# BaiDoXe_CamBien.net
KiCad netlist of a schematic drawn in Altium Designer
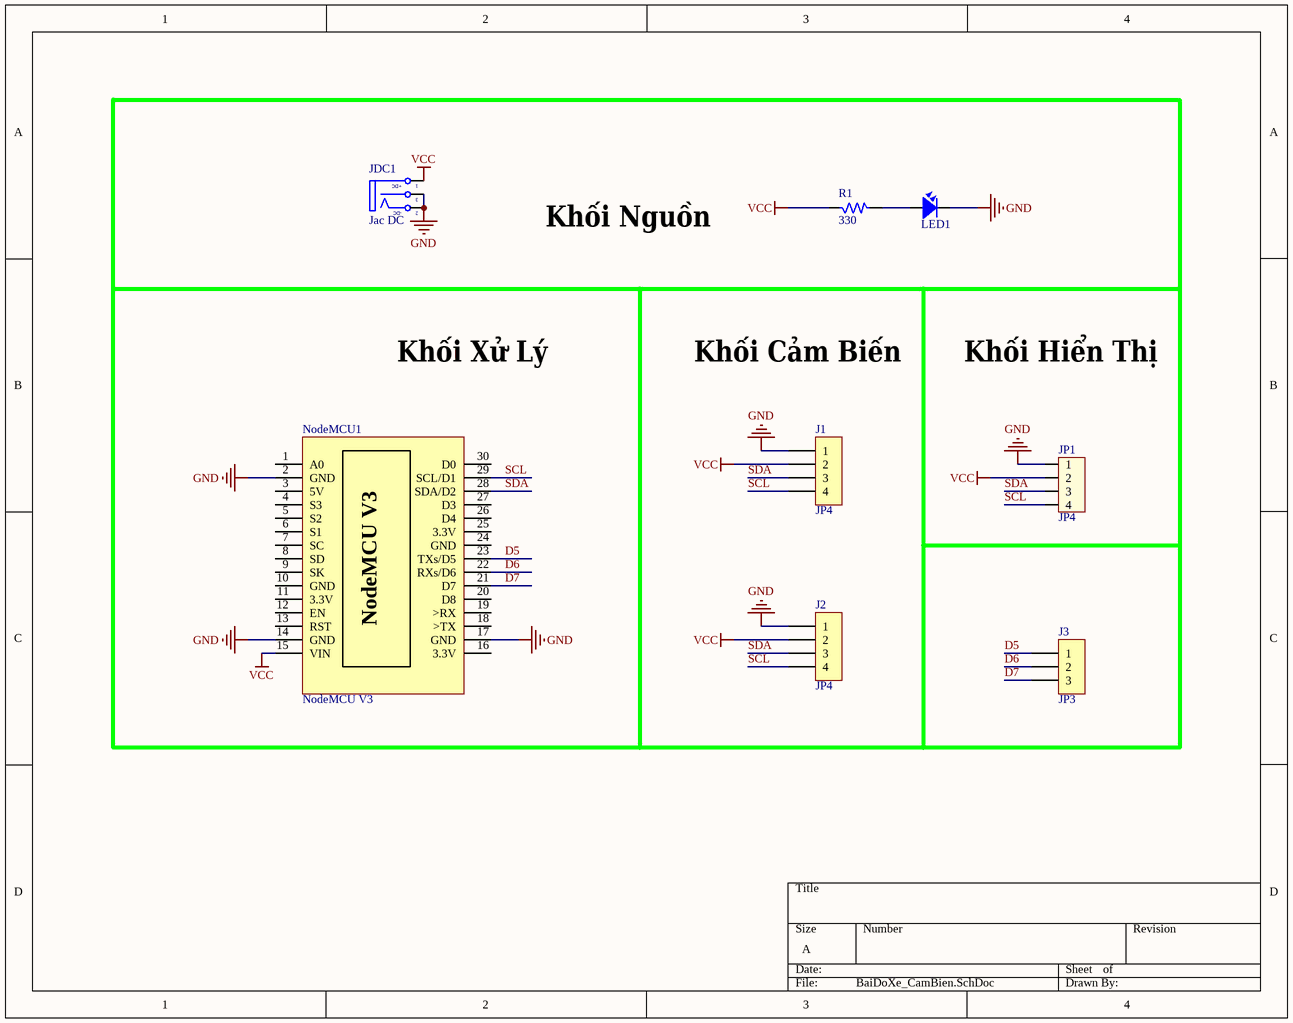
[diagram p0: BaiDoXe_CamBien.SchDoc]

(export (version "E")
  (design (tool "Eeschema 10.0.6"))
  (components
    (comp (ref "J1")
      (value "JP4")
      (footprint "JUMP DON 4")
      (description "JUMP DON DUC 2.54")
      (libsource (lib "LinhKienMCU.com") (part "JUMP 4"))
    )
    (comp (ref "J2")
      (value "JP4")
      (footprint "JUMP DON 4")
      (description "JUMP DON DUC 2.54")
      (libsource (lib "LinhKienMCU.com") (part "JUMP 4"))
    )
    (comp (ref "J3")
      (value "JP3")
      (footprint "JUMP DON 3")
      (description "JUMP DON DUC 2.54")
      (libsource (lib "LinhKienMCU.com") (part "JUMP 3"))
    )
    (comp (ref "JDC1")
      (value "Jac DC")
      (footprint "DC-IN")
      (description "Jac DC input")
      (libsource (lib "syhaunguyen") (part "DCIN"))
    )
    (comp (ref "JP1")
      (value "JP4")
      (footprint "CON4")
      (description "Connector 4")
      (libsource (lib "syhaunguyen") (part "Con4"))
    )
    (comp (ref "LED1")
      (value "LED")
      (footprint "LED-5-BLUE")
      (description "LED Single colour Green and Red")
      (libsource (lib "syhaunguyen") (part "LED"))
    )
    (comp (ref "NodeMCU1")
      (value "NodeMCU V3")
      (footprint "NodeMCU-V3")
      (libsource (lib "TDX_Local_LIbrary") (part "NodeMCU-V3"))
    )
    (comp (ref "R1")
      (value "330")
      (footprint "res_0805")
      (description "TRO DAN 0805")
      (libsource (lib "LinhKienMCU.com") (part "RES 0805"))
    )
  )
  (nets
    (net (code "1") (name "/D5") (class "Default")
      (node (ref "J3") (pin "1") (pinfunction "1_1") (pintype "passive"))
      (node (ref "NodeMCU1") (pin "23") (pinfunction "TXs/D5_23") (pintype "passive"))
    )
    (net (code "2") (name "/D6") (class "Default")
      (node (ref "J3") (pin "2") (pinfunction "2_2") (pintype "passive"))
      (node (ref "NodeMCU1") (pin "22") (pinfunction "RXs/D6_22") (pintype "passive"))
    )
    (net (code "3") (name "/D7") (class "Default")
      (node (ref "J3") (pin "3") (pinfunction "3_3") (pintype "passive"))
      (node (ref "NodeMCU1") (pin "21") (pinfunction "D7_21") (pintype "passive"))
    )
    (net (code "4") (name "/SCL") (class "Default")
      (node (ref "J1") (pin "4") (pinfunction "4_4") (pintype "passive"))
      (node (ref "J2") (pin "4") (pinfunction "4_4") (pintype "passive"))
      (node (ref "JP1") (pin "4") (pinfunction "4_4") (pintype "passive"))
      (node (ref "NodeMCU1") (pin "29") (pinfunction "SCL/D1_29") (pintype "passive"))
    )
    (net (code "5") (name "/SDA") (class "Default")
      (node (ref "J1") (pin "3") (pinfunction "3_3") (pintype "passive"))
      (node (ref "J2") (pin "3") (pinfunction "3_3") (pintype "passive"))
      (node (ref "JP1") (pin "3") (pinfunction "3_3") (pintype "passive"))
      (node (ref "NodeMCU1") (pin "28") (pinfunction "SDA/D2_28") (pintype "passive"))
    )
    (net (code "6") (name "GND") (class "Default")
      (node (ref "J1") (pin "1") (pinfunction "1_1") (pintype "passive"))
      (node (ref "J2") (pin "1") (pinfunction "1_1") (pintype "passive"))
      (node (ref "JDC1") (pin "2") (pinfunction "TN_2") (pintype "passive"))
      (node (ref "JDC1") (pin "3") (pinfunction "S_3") (pintype "power_in"))
      (node (ref "JP1") (pin "1") (pinfunction "1_1") (pintype "passive"))
      (node (ref "LED1") (pin "2") (pinfunction "2_2") (pintype "passive"))
      (node (ref "NodeMCU1") (pin "14") (pinfunction "GND_14") (pintype "passive"))
      (node (ref "NodeMCU1") (pin "17") (pinfunction "GND_17") (pintype "passive"))
      (node (ref "NodeMCU1") (pin "2") (pinfunction "GND_2") (pintype "passive"))
    )
    (net (code "7") (name "Net-(LED1-Pad1)") (class "Default")
      (node (ref "LED1") (pin "1") (pinfunction "1_1") (pintype "passive"))
      (node (ref "R1") (pin "2") (pinfunction "2_2") (pintype "passive"))
    )
    (net (code "8") (name "VCC") (class "Default")
      (node (ref "J1") (pin "2") (pinfunction "2_2") (pintype "passive"))
      (node (ref "J2") (pin "2") (pinfunction "2_2") (pintype "passive"))
      (node (ref "JDC1") (pin "1") (pinfunction "T_1") (pintype "passive"))
      (node (ref "JP1") (pin "2") (pinfunction "2_2") (pintype "passive"))
      (node (ref "NodeMCU1") (pin "15") (pinfunction "VIN_15") (pintype "passive"))
      (node (ref "R1") (pin "1") (pinfunction "1_1") (pintype "passive"))
    )
    (net (code "9") (name "unconnected-(NodeMCU1-3.3V-Pad11)") (class "Default")
      (node (ref "NodeMCU1") (pin "11") (pinfunction "3.3V_11") (pintype "passive"))
    )
    (net (code "10") (name "unconnected-(NodeMCU1-3.3V-Pad16)") (class "Default")
      (node (ref "NodeMCU1") (pin "16") (pinfunction "3.3V_16") (pintype "passive"))
    )
    (net (code "11") (name "unconnected-(NodeMCU1-3.3V-Pad25)") (class "Default")
      (node (ref "NodeMCU1") (pin "25") (pinfunction "3.3V_25") (pintype "passive"))
    )
    (net (code "12") (name "unconnected-(NodeMCU1-5V-Pad3)") (class "Default")
      (node (ref "NodeMCU1") (pin "3") (pinfunction "5V_3") (pintype "passive"))
    )
    (net (code "13") (name "unconnected-(NodeMCU1->RX-Pad19)") (class "Default")
      (node (ref "NodeMCU1") (pin "19") (pinfunction ">RX_19") (pintype "passive"))
    )
    (net (code "14") (name "unconnected-(NodeMCU1->TX-Pad18)") (class "Default")
      (node (ref "NodeMCU1") (pin "18") (pinfunction ">TX_18") (pintype "passive"))
    )
    (net (code "15") (name "unconnected-(NodeMCU1-A0-Pad1)") (class "Default")
      (node (ref "NodeMCU1") (pin "1") (pinfunction "A0_1") (pintype "passive"))
    )
    (net (code "16") (name "unconnected-(NodeMCU1-D0-Pad30)") (class "Default")
      (node (ref "NodeMCU1") (pin "30") (pinfunction "D0_30") (pintype "passive"))
    )
    (net (code "17") (name "unconnected-(NodeMCU1-D3-Pad27)") (class "Default")
      (node (ref "NodeMCU1") (pin "27") (pinfunction "D3_27") (pintype "passive"))
    )
    (net (code "18") (name "unconnected-(NodeMCU1-D4-Pad26)") (class "Default")
      (node (ref "NodeMCU1") (pin "26") (pinfunction "D4_26") (pintype "passive"))
    )
    (net (code "19") (name "unconnected-(NodeMCU1-D8-Pad20)") (class "Default")
      (node (ref "NodeMCU1") (pin "20") (pinfunction "D8_20") (pintype "passive"))
    )
    (net (code "20") (name "unconnected-(NodeMCU1-EN-Pad12)") (class "Default")
      (node (ref "NodeMCU1") (pin "12") (pinfunction "EN_12") (pintype "passive"))
    )
    (net (code "21") (name "unconnected-(NodeMCU1-GND-Pad10)") (class "Default")
      (node (ref "NodeMCU1") (pin "10") (pinfunction "GND_10") (pintype "passive"))
    )
    (net (code "22") (name "unconnected-(NodeMCU1-GND-Pad24)") (class "Default")
      (node (ref "NodeMCU1") (pin "24") (pinfunction "GND_24") (pintype "passive"))
    )
    (net (code "23") (name "unconnected-(NodeMCU1-RST-Pad13)") (class "Default")
      (node (ref "NodeMCU1") (pin "13") (pinfunction "RST_13") (pintype "passive"))
    )
    (net (code "24") (name "unconnected-(NodeMCU1-S1-Pad6)") (class "Default")
      (node (ref "NodeMCU1") (pin "6") (pinfunction "S1_6") (pintype "passive"))
    )
    (net (code "25") (name "unconnected-(NodeMCU1-S2-Pad5)") (class "Default")
      (node (ref "NodeMCU1") (pin "5") (pinfunction "S2_5") (pintype "passive"))
    )
    (net (code "26") (name "unconnected-(NodeMCU1-S3-Pad4)") (class "Default")
      (node (ref "NodeMCU1") (pin "4") (pinfunction "S3_4") (pintype "passive"))
    )
    (net (code "27") (name "unconnected-(NodeMCU1-SC-Pad7)") (class "Default")
      (node (ref "NodeMCU1") (pin "7") (pinfunction "SC_7") (pintype "passive"))
    )
    (net (code "28") (name "unconnected-(NodeMCU1-SD-Pad8)") (class "Default")
      (node (ref "NodeMCU1") (pin "8") (pinfunction "SD_8") (pintype "passive"))
    )
    (net (code "29") (name "unconnected-(NodeMCU1-SK-Pad9)") (class "Default")
      (node (ref "NodeMCU1") (pin "9") (pinfunction "SK_9") (pintype "passive"))
    )
  )
)
